# ModuleCarrier-EMW3166-v1_0_0.net
KiCad netlist of a schematic drawn in EAGLE
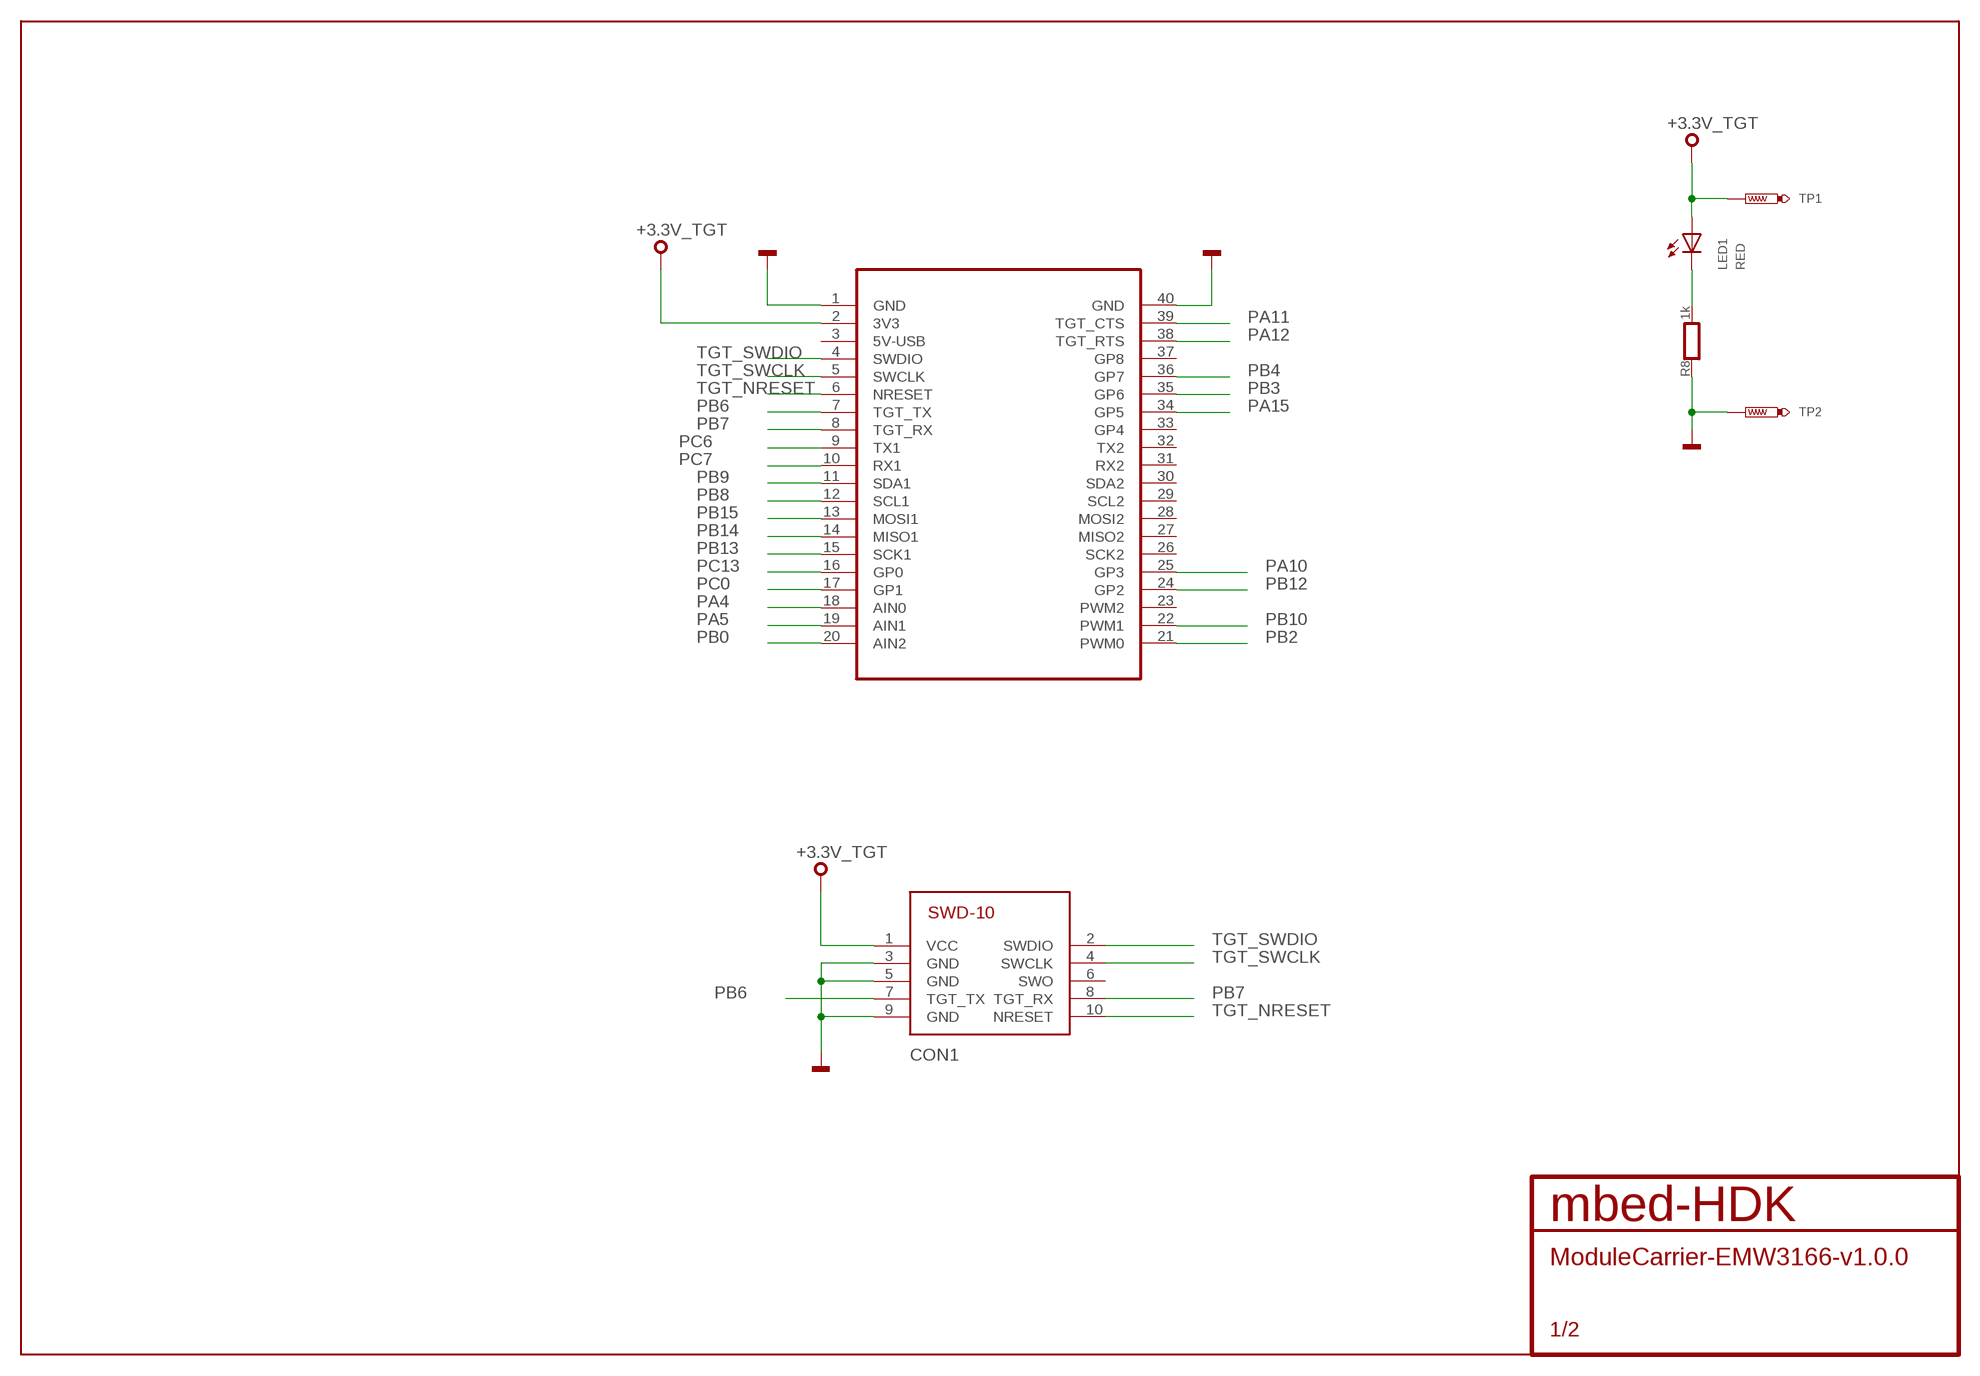
[diagram p0: schematic, sheet 1]
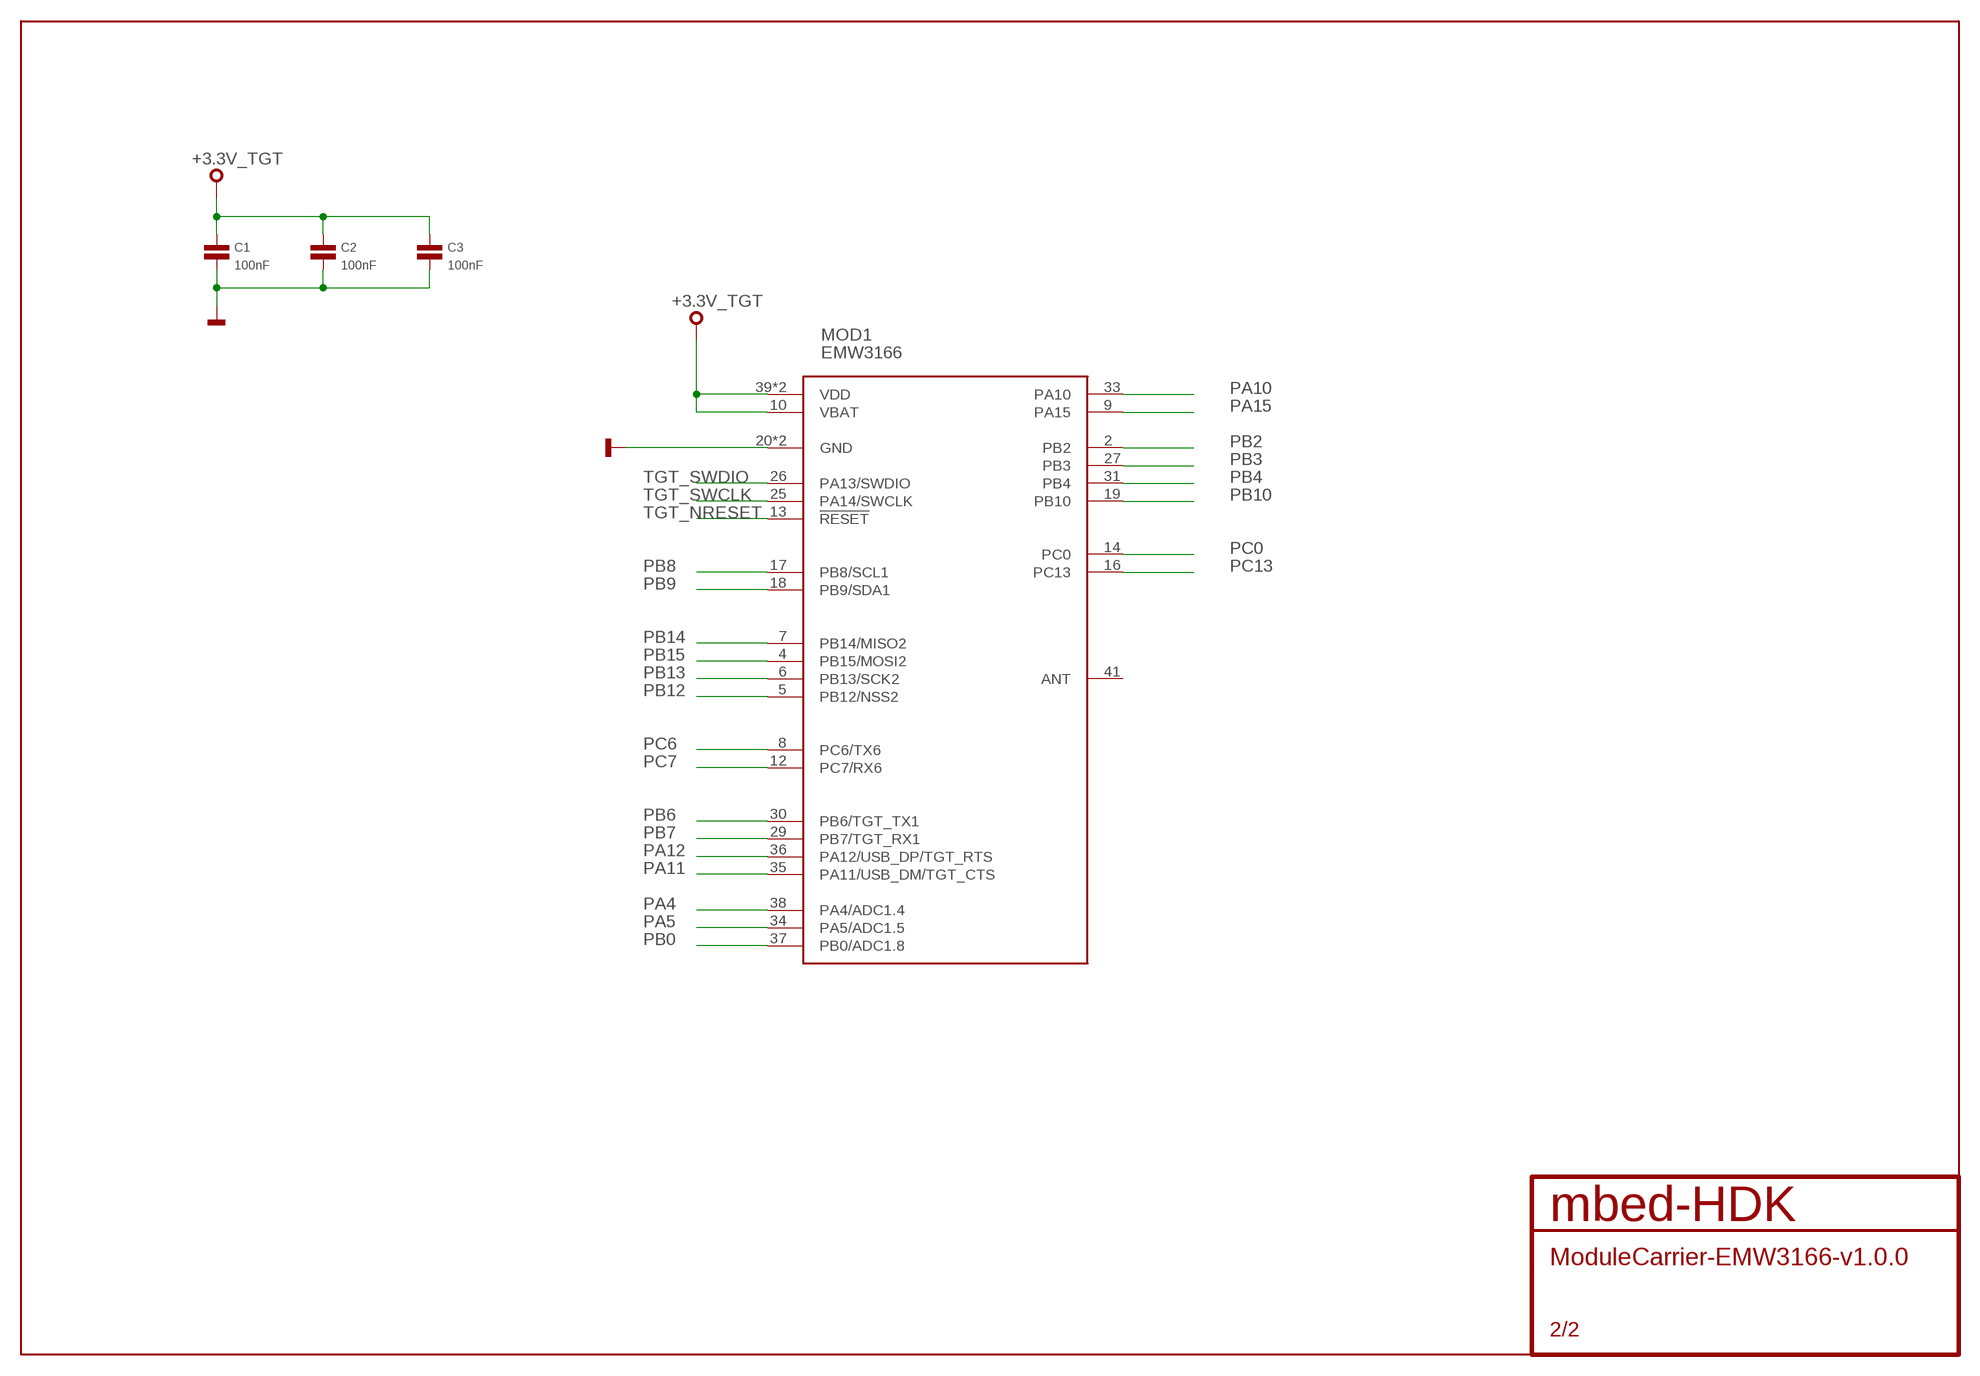
[diagram p1: schematic, sheet 2]

(export (version "E")
  (design (tool "Eeschema 10.0.6"))
  (components
    (comp (ref "C1")
      (value "100nF")
      (footprint "eagle-import:0603")
      (libsource (lib "eagle-import") (part "CAPACITOR0603"))
    )
    (comp (ref "C2")
      (value "100nF")
      (footprint "eagle-import:0603")
      (libsource (lib "eagle-import") (part "CAPACITOR0603"))
    )
    (comp (ref "C3")
      (value "100nF")
      (footprint "eagle-import:0603")
      (libsource (lib "eagle-import") (part "CAPACITOR0603"))
    )
    (comp (ref "MOD1")
      (value "EMW3166")
      (footprint "eagle-import:EMW3166")
      (libsource (lib "eagle-import") (part "EMW3166"))
    )
    (comp (ref "CON1")
      (value "SWD-10/TC2050_SMD")
      (footprint "eagle-import:FTSH-105-02")
      (libsource (lib "eagle-import") (part "SWD-10/TC2050_SMD"))
    )
    (comp (ref "LED1")
      (value "RED")
      (footprint "eagle-import:CHIPLED_0603")
      (fields (field (name "MF") "Wurth Electronics Inc"))
      (libsource (lib "eagle-import") (part "SMD_LED0603"))
    )
    (comp (ref "R8")
      (value "1k")
      (footprint "eagle-import:0603")
      (libsource (lib "eagle-import") (part "RESISTOR0603"))
    )
    (comp (ref "TP1")
      (value "TEST-POINT-50R-PTH")
      (footprint "eagle-import:TP50-PTH")
      (libsource (lib "eagle-import") (part "TEST-POINT-50R-PTH"))
    )
    (comp (ref "TP2")
      (value "TEST-POINT-50R-PTH")
      (footprint "eagle-import:TP50-PTH")
      (libsource (lib "eagle-import") (part "TEST-POINT-50R-PTH"))
    )
    (comp (ref "U$1")
      (value "MODULE_DAUGHTER")
      (footprint "eagle-import:MODULE_DAUGHTER")
      (libsource (lib "eagle-import") (part "MODULE_DAUGHTER"))
    )
  )
  (nets
    (net (code "1") (name "+3.3V_TGT") (class "Default")
      (node (ref "C1") (pin "1") (pinfunction "P$1_1") (pintype "passive"))
      (node (ref "C2") (pin "1") (pinfunction "P$1_1") (pintype "passive"))
      (node (ref "C3") (pin "1") (pinfunction "P$1_1") (pintype "passive"))
      (node (ref "CON1") (pin "1") (pinfunction "VCC_1") (pintype "bidirectional"))
      (node (ref "LED1") (pin "A") (pinfunction "A_A") (pintype "passive"))
      (node (ref "MOD1") (pin "10") (pinfunction "VBAT_10") (pintype "bidirectional"))
      (node (ref "MOD1") (pin "39") (pinfunction "VDD_39") (pintype "bidirectional"))
      (node (ref "MOD1") (pin "40") (pinfunction "VDD_40") (pintype "bidirectional"))
      (node (ref "TP1") (pin "TP") (pinfunction "TP_TP") (pintype "input"))
      (node (ref "U$1") (pin "2") (pinfunction "3V3_2") (pintype "bidirectional"))
    )
    (net (code "2") (name "GND") (class "Default")
      (node (ref "C1") (pin "2") (pinfunction "P$2_2") (pintype "passive"))
      (node (ref "C2") (pin "2") (pinfunction "P$2_2") (pintype "passive"))
      (node (ref "C3") (pin "2") (pinfunction "P$2_2") (pintype "passive"))
      (node (ref "CON1") (pin "3") (pinfunction "GND_3") (pintype "bidirectional"))
      (node (ref "CON1") (pin "5") (pinfunction "GND_5") (pintype "bidirectional"))
      (node (ref "CON1") (pin "9") (pinfunction "GND_9") (pintype "bidirectional"))
      (node (ref "MOD1") (pin "20") (pinfunction "GND_20") (pintype "bidirectional"))
      (node (ref "MOD1") (pin "21") (pinfunction "GND_21") (pintype "bidirectional"))
      (node (ref "R8") (pin "1") (pinfunction "P$1_1") (pintype "passive"))
      (node (ref "TP2") (pin "TP") (pinfunction "TP_TP") (pintype "input"))
      (node (ref "U$1") (pin "1") (pinfunction "GND_1") (pintype "bidirectional"))
      (node (ref "U$1") (pin "40") (pinfunction "GND_40") (pintype "bidirectional"))
    )
    (net (code "3") (name "Net-(R8-P$2)") (class "Default")
      (node (ref "LED1") (pin "C") (pinfunction "C_C") (pintype "passive"))
      (node (ref "R8") (pin "2") (pinfunction "P$2_2") (pintype "passive"))
    )
    (net (code "4") (name "PA4") (class "Default")
      (node (ref "MOD1") (pin "38") (pinfunction "PA4/ADC1.4_38") (pintype "bidirectional"))
      (node (ref "U$1") (pin "18") (pinfunction "AIN0_18") (pintype "bidirectional"))
    )
    (net (code "5") (name "PA5") (class "Default")
      (node (ref "MOD1") (pin "34") (pinfunction "PA5/ADC1.5_34") (pintype "bidirectional"))
      (node (ref "U$1") (pin "19") (pinfunction "AIN1_19") (pintype "bidirectional"))
    )
    (net (code "6") (name "PA10") (class "Default")
      (node (ref "MOD1") (pin "33") (pinfunction "PA10_33") (pintype "bidirectional"))
      (node (ref "U$1") (pin "25") (pinfunction "GP3_25") (pintype "bidirectional"))
    )
    (net (code "7") (name "PA11") (class "Default")
      (node (ref "MOD1") (pin "35") (pinfunction "PA11/USB_DM/TGT_CTS_35") (pintype "bidirectional"))
      (node (ref "U$1") (pin "39") (pinfunction "TGT_CTS_39") (pintype "bidirectional"))
    )
    (net (code "8") (name "PA12") (class "Default")
      (node (ref "MOD1") (pin "36") (pinfunction "PA12/USB_DP/TGT_RTS_36") (pintype "bidirectional"))
      (node (ref "U$1") (pin "38") (pinfunction "TGT_RTS_38") (pintype "bidirectional"))
    )
    (net (code "9") (name "PA15") (class "Default")
      (node (ref "MOD1") (pin "9") (pinfunction "PA15_9") (pintype "bidirectional"))
      (node (ref "U$1") (pin "34") (pinfunction "GP5_34") (pintype "bidirectional"))
    )
    (net (code "10") (name "PB0") (class "Default")
      (node (ref "MOD1") (pin "37") (pinfunction "PB0/ADC1.8_37") (pintype "bidirectional"))
      (node (ref "U$1") (pin "20") (pinfunction "AIN2_20") (pintype "bidirectional"))
    )
    (net (code "11") (name "PB2") (class "Default")
      (node (ref "MOD1") (pin "2") (pinfunction "PB2_2") (pintype "bidirectional"))
      (node (ref "U$1") (pin "21") (pinfunction "PWM0_21") (pintype "bidirectional"))
    )
    (net (code "12") (name "PB3") (class "Default")
      (node (ref "MOD1") (pin "27") (pinfunction "PB3_27") (pintype "bidirectional"))
      (node (ref "U$1") (pin "35") (pinfunction "GP6_35") (pintype "bidirectional"))
    )
    (net (code "13") (name "PB4") (class "Default")
      (node (ref "MOD1") (pin "31") (pinfunction "PB4_31") (pintype "bidirectional"))
      (node (ref "U$1") (pin "36") (pinfunction "GP7_36") (pintype "bidirectional"))
    )
    (net (code "14") (name "PB6") (class "Default")
      (node (ref "CON1") (pin "7") (pinfunction "TGT_TX_7") (pintype "bidirectional"))
      (node (ref "MOD1") (pin "30") (pinfunction "PB6/TGT_TX1_30") (pintype "bidirectional"))
      (node (ref "U$1") (pin "7") (pinfunction "TGT_TX_7") (pintype "bidirectional"))
    )
    (net (code "15") (name "PB7") (class "Default")
      (node (ref "CON1") (pin "8") (pinfunction "TGT_RX_8") (pintype "bidirectional"))
      (node (ref "MOD1") (pin "29") (pinfunction "PB7/TGT_RX1_29") (pintype "bidirectional"))
      (node (ref "U$1") (pin "8") (pinfunction "TGT_RX_8") (pintype "bidirectional"))
    )
    (net (code "16") (name "PB8") (class "Default")
      (node (ref "MOD1") (pin "17") (pinfunction "PB8/SCL1_17") (pintype "bidirectional"))
      (node (ref "U$1") (pin "12") (pinfunction "SCL1_12") (pintype "bidirectional"))
    )
    (net (code "17") (name "PB9") (class "Default")
      (node (ref "MOD1") (pin "18") (pinfunction "PB9/SDA1_18") (pintype "bidirectional"))
      (node (ref "U$1") (pin "11") (pinfunction "SDA1_11") (pintype "bidirectional"))
    )
    (net (code "18") (name "PB10") (class "Default")
      (node (ref "MOD1") (pin "19") (pinfunction "PB10_19") (pintype "bidirectional"))
      (node (ref "U$1") (pin "22") (pinfunction "PWM1_22") (pintype "bidirectional"))
    )
    (net (code "19") (name "PB12") (class "Default")
      (node (ref "MOD1") (pin "5") (pinfunction "PB12/NSS2_5") (pintype "bidirectional"))
      (node (ref "U$1") (pin "24") (pinfunction "GP2_24") (pintype "bidirectional"))
    )
    (net (code "20") (name "PB13") (class "Default")
      (node (ref "MOD1") (pin "6") (pinfunction "PB13/SCK2_6") (pintype "bidirectional"))
      (node (ref "U$1") (pin "15") (pinfunction "SCK1_15") (pintype "bidirectional"))
    )
    (net (code "21") (name "PB14") (class "Default")
      (node (ref "MOD1") (pin "7") (pinfunction "PB14/MISO2_7") (pintype "bidirectional"))
      (node (ref "U$1") (pin "14") (pinfunction "MISO1_14") (pintype "bidirectional"))
    )
    (net (code "22") (name "PB15") (class "Default")
      (node (ref "MOD1") (pin "4") (pinfunction "PB15/MOSI2_4") (pintype "bidirectional"))
      (node (ref "U$1") (pin "13") (pinfunction "MOSI1_13") (pintype "bidirectional"))
    )
    (net (code "23") (name "PC0") (class "Default")
      (node (ref "MOD1") (pin "14") (pinfunction "PC0_14") (pintype "bidirectional"))
      (node (ref "U$1") (pin "17") (pinfunction "GP1_17") (pintype "bidirectional"))
    )
    (net (code "24") (name "PC6") (class "Default")
      (node (ref "MOD1") (pin "8") (pinfunction "PC6/TX6_8") (pintype "bidirectional"))
      (node (ref "U$1") (pin "9") (pinfunction "TX1_9") (pintype "bidirectional"))
    )
    (net (code "25") (name "PC7") (class "Default")
      (node (ref "MOD1") (pin "12") (pinfunction "PC7/RX6_12") (pintype "bidirectional"))
      (node (ref "U$1") (pin "10") (pinfunction "RX1_10") (pintype "bidirectional"))
    )
    (net (code "26") (name "PC13") (class "Default")
      (node (ref "MOD1") (pin "16") (pinfunction "PC13_16") (pintype "bidirectional"))
      (node (ref "U$1") (pin "16") (pinfunction "GP0_16") (pintype "bidirectional"))
    )
    (net (code "27") (name "TGT_NRESET") (class "Default")
      (node (ref "CON1") (pin "10") (pinfunction "NRESET_10") (pintype "bidirectional"))
      (node (ref "MOD1") (pin "13") (pinfunction "~{RESET}_13") (pintype "bidirectional"))
      (node (ref "U$1") (pin "6") (pinfunction "NRESET_6") (pintype "bidirectional"))
    )
    (net (code "28") (name "TGT_SWCLK") (class "Default")
      (node (ref "CON1") (pin "4") (pinfunction "SWCLK_4") (pintype "bidirectional"))
      (node (ref "MOD1") (pin "25") (pinfunction "PA14/SWCLK_25") (pintype "bidirectional"))
      (node (ref "U$1") (pin "5") (pinfunction "SWCLK_5") (pintype "bidirectional"))
    )
    (net (code "29") (name "TGT_SWDIO") (class "Default")
      (node (ref "CON1") (pin "2") (pinfunction "SWDIO_2") (pintype "bidirectional"))
      (node (ref "MOD1") (pin "26") (pinfunction "PA13/SWDIO_26") (pintype "bidirectional"))
      (node (ref "U$1") (pin "4") (pinfunction "SWDIO_4") (pintype "bidirectional"))
    )
    (net (code "30") (name "unconnected-(CON1-SWO-Pad6)") (class "Default")
      (node (ref "CON1") (pin "6") (pinfunction "SWO_6") (pintype "bidirectional"))
    )
    (net (code "31") (name "unconnected-(MOD1-ANT-Pad41)") (class "Default")
      (node (ref "MOD1") (pin "41") (pinfunction "ANT_41") (pintype "bidirectional"))
    )
    (net (code "32") (name "unconnected-(U$1-5V-USB-Pad3)") (class "Default")
      (node (ref "U$1") (pin "3") (pinfunction "5V-USB_3") (pintype "bidirectional"))
    )
    (net (code "33") (name "unconnected-(U$1-GP4-Pad33)") (class "Default")
      (node (ref "U$1") (pin "33") (pinfunction "GP4_33") (pintype "bidirectional"))
    )
    (net (code "34") (name "unconnected-(U$1-GP8-Pad37)") (class "Default")
      (node (ref "U$1") (pin "37") (pinfunction "GP8_37") (pintype "bidirectional"))
    )
    (net (code "35") (name "unconnected-(U$1-MISO2-Pad27)") (class "Default")
      (node (ref "U$1") (pin "27") (pinfunction "MISO2_27") (pintype "bidirectional"))
    )
    (net (code "36") (name "unconnected-(U$1-MOSI2-Pad28)") (class "Default")
      (node (ref "U$1") (pin "28") (pinfunction "MOSI2_28") (pintype "bidirectional"))
    )
    (net (code "37") (name "unconnected-(U$1-PWM2-Pad23)") (class "Default")
      (node (ref "U$1") (pin "23") (pinfunction "PWM2_23") (pintype "bidirectional"))
    )
    (net (code "38") (name "unconnected-(U$1-RX2-Pad31)") (class "Default")
      (node (ref "U$1") (pin "31") (pinfunction "RX2_31") (pintype "bidirectional"))
    )
    (net (code "39") (name "unconnected-(U$1-SCK2-Pad26)") (class "Default")
      (node (ref "U$1") (pin "26") (pinfunction "SCK2_26") (pintype "bidirectional"))
    )
    (net (code "40") (name "unconnected-(U$1-SCL2-Pad29)") (class "Default")
      (node (ref "U$1") (pin "29") (pinfunction "SCL2_29") (pintype "bidirectional"))
    )
    (net (code "41") (name "unconnected-(U$1-SDA2-Pad30)") (class "Default")
      (node (ref "U$1") (pin "30") (pinfunction "SDA2_30") (pintype "bidirectional"))
    )
    (net (code "42") (name "unconnected-(U$1-TX2-Pad32)") (class "Default")
      (node (ref "U$1") (pin "32") (pinfunction "TX2_32") (pintype "bidirectional"))
    )
  )
)
